# sheet1.net
KiCad netlist of a schematic drawn in EAGLE
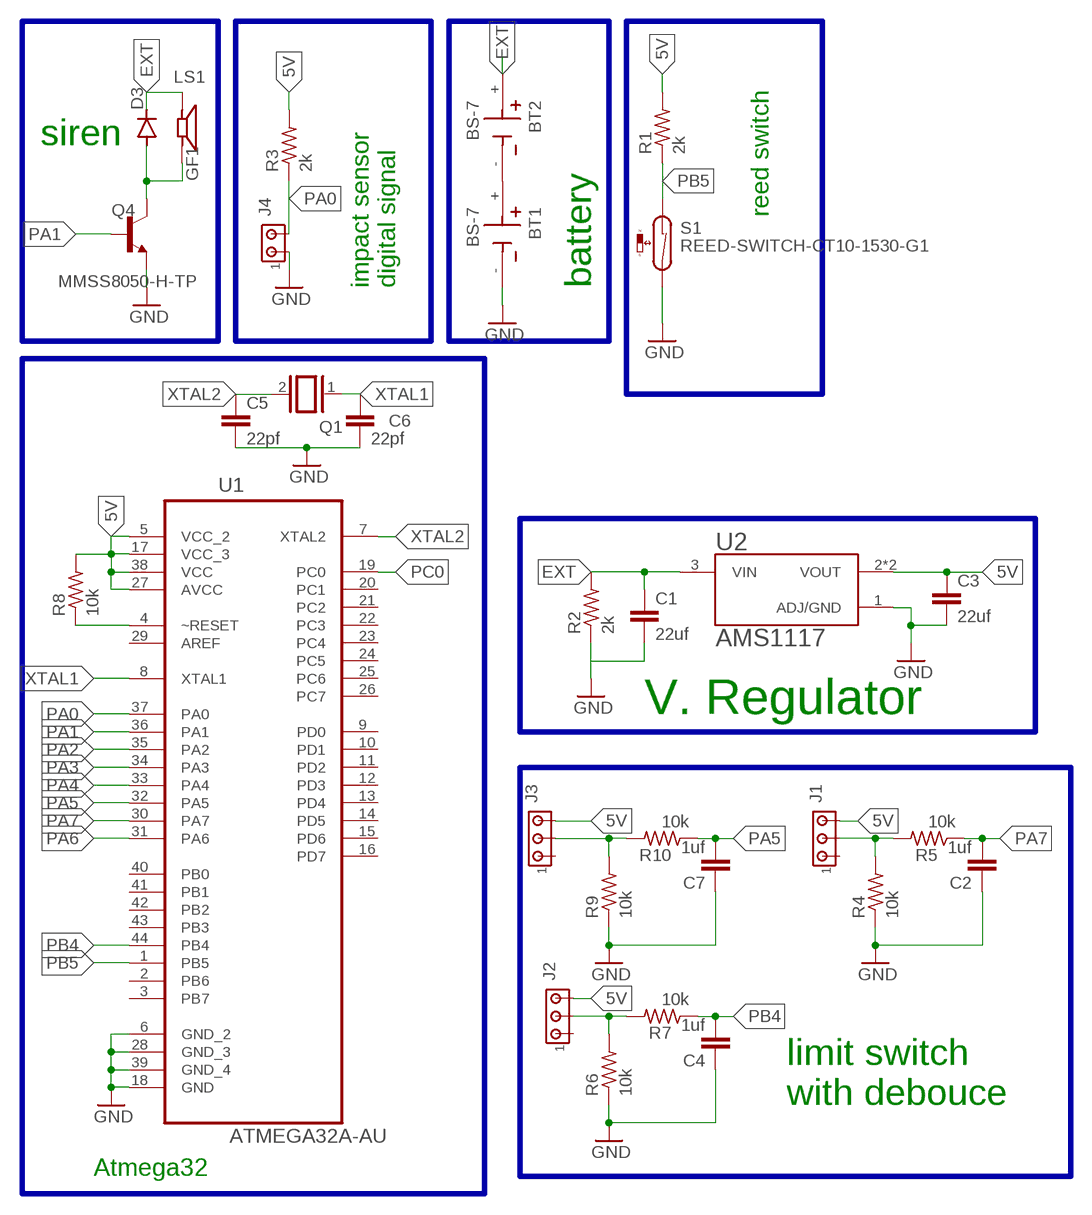
[diagram p0: schematic, sheet 1]

(export (version "E")
  (design (tool "Eeschema 10.0.6"))
  (components
    (comp (ref "BT1")
      (value "BS-7")
      (footprint "eagle-import:BAT_BS-7")
      (fields (field (name "MF") "MPD _Memory"))
      (libsource (lib "eagle-import") (part "BS-7"))
    )
    (comp (ref "BT2")
      (value "BS-7")
      (footprint "eagle-import:BAT_BS-7")
      (fields (field (name "MF") "MPD _Memory"))
      (libsource (lib "eagle-import") (part "BS-7"))
    )
    (comp (ref "C1")
      (value "22uf")
      (footprint "eagle-import:C1206")
      (libsource (lib "eagle-import") (part "C-EUC1206"))
    )
    (comp (ref "C2")
      (value "1uf")
      (footprint "eagle-import:C1206")
      (libsource (lib "eagle-import") (part "C-EUC1206"))
    )
    (comp (ref "C3")
      (value "22uf")
      (footprint "eagle-import:C1206")
      (libsource (lib "eagle-import") (part "C-EUC1206"))
    )
    (comp (ref "C4")
      (value "1uf")
      (footprint "eagle-import:C1206")
      (libsource (lib "eagle-import") (part "C-EUC1206"))
    )
    (comp (ref "C5")
      (value "22pf")
      (footprint "eagle-import:C1206")
      (libsource (lib "eagle-import") (part "C-EUC1206"))
    )
    (comp (ref "C6")
      (value "22pf")
      (footprint "eagle-import:C1206")
      (libsource (lib "eagle-import") (part "C-EUC1206"))
    )
    (comp (ref "C7")
      (value "1uf")
      (footprint "eagle-import:C1206")
      (libsource (lib "eagle-import") (part "C-EUC1206"))
    )
    (comp (ref "D3")
      (value "GF1")
      (footprint "eagle-import:SMA-DO214AC")
      (libsource (lib "eagle-import") (part "GF1"))
    )
    (comp (ref "J1")
      (value "MTA03-100")
      (footprint "eagle-import:10X03MTA")
      (libsource (lib "eagle-import") (part "MTA03-100"))
    )
    (comp (ref "J2")
      (value "MTA03-100")
      (footprint "eagle-import:10X03MTA")
      (libsource (lib "eagle-import") (part "MTA03-100"))
    )
    (comp (ref "J3")
      (value "MTA03-100")
      (footprint "eagle-import:10X03MTA")
      (libsource (lib "eagle-import") (part "MTA03-100"))
    )
    (comp (ref "J4")
      (value "MTA02-100")
      (footprint "eagle-import:10X02MTA")
      (libsource (lib "eagle-import") (part "MTA02-100"))
    )
    (comp (ref "LS1")
      (value "CEP-1152")
      (footprint "eagle-import:CUI_CEP-1152")
      (fields (field (name "MF") "CUI Devices"))
      (libsource (lib "eagle-import") (part "CEP-1152"))
    )
    (comp (ref "Q1")
      (value "XTAL/S")
      (footprint "eagle-import:QS")
      (libsource (lib "eagle-import") (part "XTAL/S"))
    )
    (comp (ref "Q4")
      (value "MMSS8050-H-TP")
      (footprint "eagle-import:TRANS_MMSS8050-H-TP")
      (fields (field (name "MF") "Micro Commercial"))
      (libsource (lib "eagle-import") (part "MMSS8050-H-TP"))
    )
    (comp (ref "R1")
      (value "2k")
      (footprint "eagle-import:R1206")
      (libsource (lib "eagle-import") (part "R-US_R1206"))
    )
    (comp (ref "R2")
      (value "2k")
      (footprint "eagle-import:R1206")
      (libsource (lib "eagle-import") (part "R-US_R1206"))
    )
    (comp (ref "R3")
      (value "2k")
      (footprint "eagle-import:R1206")
      (libsource (lib "eagle-import") (part "R-US_R1206"))
    )
    (comp (ref "R4")
      (value "10k")
      (footprint "eagle-import:R1206")
      (libsource (lib "eagle-import") (part "R-US_R1206"))
    )
    (comp (ref "R5")
      (value "10k")
      (footprint "eagle-import:R1206")
      (libsource (lib "eagle-import") (part "R-US_R1206"))
    )
    (comp (ref "R6")
      (value "10k")
      (footprint "eagle-import:R1206")
      (libsource (lib "eagle-import") (part "R-US_R1206"))
    )
    (comp (ref "R7")
      (value "10k")
      (footprint "eagle-import:R1206")
      (libsource (lib "eagle-import") (part "R-US_R1206"))
    )
    (comp (ref "R8")
      (value "10k")
      (footprint "eagle-import:R1206")
      (libsource (lib "eagle-import") (part "R-US_R1206"))
    )
    (comp (ref "R9")
      (value "10k")
      (footprint "eagle-import:R1206")
      (libsource (lib "eagle-import") (part "R-US_R1206"))
    )
    (comp (ref "R10")
      (value "10k")
      (footprint "eagle-import:R1206")
      (libsource (lib "eagle-import") (part "R-US_R1206"))
    )
    (comp (ref "S1")
      (value "REED-SWITCH-CT10-1530-G1")
      (footprint "eagle-import:CT10-G1")
      (fields (field (name "MF") "COTO TECHNOLOGY") (field (name "MPN") "CT10-1530-G1"))
      (libsource (lib "eagle-import") (part "REED-SWITCH-CT10-1530-G1"))
    )
    (comp (ref "U1")
      (value "ATMEGA32A-AU")
      (footprint "eagle-import:QFP80P1200X1200X120-44N")
      (fields (field (name "MF") "Microchip"))
      (libsource (lib "eagle-import") (part "ATMEGA32A-AU"))
    )
    (comp (ref "U2")
      (value "AMS1117")
      (footprint "eagle-import:SOT229P700X180-4N")
      (fields (field (name "MF") "Seeed Technology"))
      (libsource (lib "eagle-import") (part "AMS1117"))
    )
  )
  (nets
    (net (code "1") (name "5V") (class "Default")
      (node (ref "C3") (pin "1") (pinfunction "1_1") (pintype "passive"))
      (node (ref "J1") (pin "3") (pinfunction "3_3") (pintype "passive"))
      (node (ref "J2") (pin "3") (pinfunction "3_3") (pintype "passive"))
      (node (ref "J3") (pin "3") (pinfunction "3_3") (pintype "passive"))
      (node (ref "R1") (pin "2") (pinfunction "2_2") (pintype "passive"))
      (node (ref "R3") (pin "2") (pinfunction "2_2") (pintype "passive"))
      (node (ref "R8") (pin "2") (pinfunction "2_2") (pintype "passive"))
      (node (ref "U1") (pin "17") (pinfunction "VCC_3_17") (pintype "power_in"))
      (node (ref "U1") (pin "27") (pinfunction "AVCC_27") (pintype "power_in"))
      (node (ref "U1") (pin "38") (pinfunction "VCC_38") (pintype "power_in"))
      (node (ref "U1") (pin "5") (pinfunction "VCC_2_5") (pintype "power_in"))
      (node (ref "U2") (pin "2") (pinfunction "VOUT_2") (pintype "output"))
      (node (ref "U2") (pin "4") (pinfunction "VOUT_4") (pintype "output"))
    )
    (net (code "2") (name "EXT") (class "Default")
      (node (ref "BT2") (pin "+") (pinfunction "+_+") (pintype "passive"))
      (node (ref "C1") (pin "1") (pinfunction "1_1") (pintype "passive"))
      (node (ref "D3") (pin "K") (pinfunction "C_K") (pintype "passive"))
      (node (ref "LS1") (pin "1") (pinfunction "1_1") (pintype "passive"))
      (node (ref "R2") (pin "2") (pinfunction "2_2") (pintype "passive"))
      (node (ref "U2") (pin "3") (pinfunction "VIN_3") (pintype "input"))
    )
    (net (code "3") (name "GND") (class "Default")
      (node (ref "BT1") (pin "-") (pinfunction "-_-") (pintype "passive"))
      (node (ref "C1") (pin "2") (pinfunction "2_2") (pintype "passive"))
      (node (ref "C2") (pin "1") (pinfunction "1_1") (pintype "passive"))
      (node (ref "C3") (pin "2") (pinfunction "2_2") (pintype "passive"))
      (node (ref "C4") (pin "1") (pinfunction "1_1") (pintype "passive"))
      (node (ref "C5") (pin "2") (pinfunction "2_2") (pintype "passive"))
      (node (ref "C6") (pin "2") (pinfunction "2_2") (pintype "passive"))
      (node (ref "C7") (pin "1") (pinfunction "1_1") (pintype "passive"))
      (node (ref "J4") (pin "1") (pinfunction "1_1") (pintype "passive"))
      (node (ref "Q4") (pin "2") (pinfunction "E_2") (pintype "passive"))
      (node (ref "R2") (pin "1") (pinfunction "1_1") (pintype "passive"))
      (node (ref "R4") (pin "1") (pinfunction "1_1") (pintype "passive"))
      (node (ref "R6") (pin "1") (pinfunction "1_1") (pintype "passive"))
      (node (ref "R9") (pin "1") (pinfunction "1_1") (pintype "passive"))
      (node (ref "S1") (pin "2") (pinfunction "2_2") (pintype "passive"))
      (node (ref "U1") (pin "18") (pinfunction "GND_18") (pintype "passive"))
      (node (ref "U1") (pin "28") (pinfunction "GND_3_28") (pintype "passive"))
      (node (ref "U1") (pin "39") (pinfunction "GND_4_39") (pintype "passive"))
      (node (ref "U1") (pin "6") (pinfunction "GND_2_6") (pintype "passive"))
      (node (ref "U2") (pin "1") (pinfunction "ADJ/GND_1") (pintype "power_in"))
    )
    (net (code "4") (name "Net-(BT1-Pad+)") (class "Default")
      (node (ref "BT1") (pin "+") (pinfunction "+_+") (pintype "passive"))
      (node (ref "BT2") (pin "-") (pinfunction "-_-") (pintype "passive"))
    )
    (net (code "5") (name "Net-(J1-Pad2)") (class "Default")
      (node (ref "J1") (pin "2") (pinfunction "2_2") (pintype "passive"))
      (node (ref "R4") (pin "2") (pinfunction "2_2") (pintype "passive"))
      (node (ref "R5") (pin "2") (pinfunction "2_2") (pintype "passive"))
    )
    (net (code "6") (name "Net-(J2-Pad2)") (class "Default")
      (node (ref "J2") (pin "2") (pinfunction "2_2") (pintype "passive"))
      (node (ref "R6") (pin "2") (pinfunction "2_2") (pintype "passive"))
      (node (ref "R7") (pin "2") (pinfunction "2_2") (pintype "passive"))
    )
    (net (code "7") (name "Net-(J3-Pad2)") (class "Default")
      (node (ref "J3") (pin "2") (pinfunction "2_2") (pintype "passive"))
      (node (ref "R10") (pin "2") (pinfunction "2_2") (pintype "passive"))
      (node (ref "R9") (pin "2") (pinfunction "2_2") (pintype "passive"))
    )
    (net (code "8") (name "Net-(Q4-C)") (class "Default")
      (node (ref "D3") (pin "A") (pinfunction "A_A") (pintype "passive"))
      (node (ref "LS1") (pin "2") (pinfunction "2_2") (pintype "passive"))
      (node (ref "Q4") (pin "3") (pinfunction "C_3") (pintype "passive"))
    )
    (net (code "9") (name "Net-(U1-~{RESET})") (class "Default")
      (node (ref "R8") (pin "1") (pinfunction "1_1") (pintype "passive"))
      (node (ref "U1") (pin "4") (pinfunction "~{RESET}_4") (pintype "input"))
    )
    (net (code "10") (name "PA0") (class "Default")
      (node (ref "J4") (pin "2") (pinfunction "2_2") (pintype "passive"))
      (node (ref "R3") (pin "1") (pinfunction "1_1") (pintype "passive"))
      (node (ref "U1") (pin "37") (pinfunction "PA0_37") (pintype "bidirectional"))
    )
    (net (code "11") (name "PA1") (class "Default")
      (node (ref "Q4") (pin "1") (pinfunction "B_1") (pintype "passive"))
      (node (ref "U1") (pin "36") (pinfunction "PA1_36") (pintype "bidirectional"))
    )
    (net (code "12") (name "PA2") (class "Default")
      (node (ref "U1") (pin "35") (pinfunction "PA2_35") (pintype "bidirectional"))
    )
    (net (code "13") (name "PA3") (class "Default")
      (node (ref "U1") (pin "34") (pinfunction "PA3_34") (pintype "bidirectional"))
    )
    (net (code "14") (name "PA4") (class "Default")
      (node (ref "U1") (pin "33") (pinfunction "PA4_33") (pintype "bidirectional"))
    )
    (net (code "15") (name "PA5") (class "Default")
      (node (ref "C7") (pin "2") (pinfunction "2_2") (pintype "passive"))
      (node (ref "R10") (pin "1") (pinfunction "1_1") (pintype "passive"))
      (node (ref "U1") (pin "32") (pinfunction "PA5_32") (pintype "bidirectional"))
    )
    (net (code "16") (name "PA6") (class "Default")
      (node (ref "U1") (pin "31") (pinfunction "PA6_31") (pintype "bidirectional"))
    )
    (net (code "17") (name "PA7") (class "Default")
      (node (ref "C2") (pin "2") (pinfunction "2_2") (pintype "passive"))
      (node (ref "R5") (pin "1") (pinfunction "1_1") (pintype "passive"))
      (node (ref "U1") (pin "30") (pinfunction "PA7_30") (pintype "bidirectional"))
    )
    (net (code "18") (name "PB4") (class "Default")
      (node (ref "C4") (pin "2") (pinfunction "2_2") (pintype "passive"))
      (node (ref "R7") (pin "1") (pinfunction "1_1") (pintype "passive"))
      (node (ref "U1") (pin "44") (pinfunction "PB4_44") (pintype "bidirectional"))
    )
    (net (code "19") (name "PB5") (class "Default")
      (node (ref "R1") (pin "1") (pinfunction "1_1") (pintype "passive"))
      (node (ref "S1") (pin "1") (pinfunction "1_1") (pintype "passive"))
      (node (ref "U1") (pin "1") (pinfunction "PB5_1") (pintype "bidirectional"))
    )
    (net (code "20") (name "PC0") (class "Default")
      (node (ref "U1") (pin "19") (pinfunction "PC0_19") (pintype "bidirectional"))
    )
    (net (code "21") (name "XTAL1") (class "Default")
      (node (ref "C6") (pin "1") (pinfunction "1_1") (pintype "passive"))
      (node (ref "Q1") (pin "1") (pinfunction "1_1") (pintype "passive"))
      (node (ref "U1") (pin "8") (pinfunction "XTAL1_8") (pintype "input"))
    )
    (net (code "22") (name "XTAL2") (class "Default")
      (node (ref "C5") (pin "1") (pinfunction "1_1") (pintype "passive"))
      (node (ref "Q1") (pin "2") (pinfunction "2_2") (pintype "passive"))
      (node (ref "U1") (pin "7") (pinfunction "XTAL2_7") (pintype "output"))
    )
    (net (code "23") (name "unconnected-(J1-Pad1)") (class "Default")
      (node (ref "J1") (pin "1") (pinfunction "1_1") (pintype "passive"))
    )
    (net (code "24") (name "unconnected-(J2-Pad1)") (class "Default")
      (node (ref "J2") (pin "1") (pinfunction "1_1") (pintype "passive"))
    )
    (net (code "25") (name "unconnected-(J3-Pad1)") (class "Default")
      (node (ref "J3") (pin "1") (pinfunction "1_1") (pintype "passive"))
    )
    (net (code "26") (name "unconnected-(U1-AREF-Pad29)") (class "Default")
      (node (ref "U1") (pin "29") (pinfunction "AREF_29") (pintype "input"))
    )
    (net (code "27") (name "unconnected-(U1-PB0-Pad40)") (class "Default")
      (node (ref "U1") (pin "40") (pinfunction "PB0_40") (pintype "bidirectional"))
    )
    (net (code "28") (name "unconnected-(U1-PB1-Pad41)") (class "Default")
      (node (ref "U1") (pin "41") (pinfunction "PB1_41") (pintype "bidirectional"))
    )
    (net (code "29") (name "unconnected-(U1-PB2-Pad42)") (class "Default")
      (node (ref "U1") (pin "42") (pinfunction "PB2_42") (pintype "bidirectional"))
    )
    (net (code "30") (name "unconnected-(U1-PB3-Pad43)") (class "Default")
      (node (ref "U1") (pin "43") (pinfunction "PB3_43") (pintype "bidirectional"))
    )
    (net (code "31") (name "unconnected-(U1-PB6-Pad2)") (class "Default")
      (node (ref "U1") (pin "2") (pinfunction "PB6_2") (pintype "bidirectional"))
    )
    (net (code "32") (name "unconnected-(U1-PB7-Pad3)") (class "Default")
      (node (ref "U1") (pin "3") (pinfunction "PB7_3") (pintype "bidirectional"))
    )
    (net (code "33") (name "unconnected-(U1-PC1-Pad20)") (class "Default")
      (node (ref "U1") (pin "20") (pinfunction "PC1_20") (pintype "bidirectional"))
    )
    (net (code "34") (name "unconnected-(U1-PC2-Pad21)") (class "Default")
      (node (ref "U1") (pin "21") (pinfunction "PC2_21") (pintype "bidirectional"))
    )
    (net (code "35") (name "unconnected-(U1-PC3-Pad22)") (class "Default")
      (node (ref "U1") (pin "22") (pinfunction "PC3_22") (pintype "bidirectional"))
    )
    (net (code "36") (name "unconnected-(U1-PC4-Pad23)") (class "Default")
      (node (ref "U1") (pin "23") (pinfunction "PC4_23") (pintype "bidirectional"))
    )
    (net (code "37") (name "unconnected-(U1-PC5-Pad24)") (class "Default")
      (node (ref "U1") (pin "24") (pinfunction "PC5_24") (pintype "bidirectional"))
    )
    (net (code "38") (name "unconnected-(U1-PC6-Pad25)") (class "Default")
      (node (ref "U1") (pin "25") (pinfunction "PC6_25") (pintype "bidirectional"))
    )
    (net (code "39") (name "unconnected-(U1-PC7-Pad26)") (class "Default")
      (node (ref "U1") (pin "26") (pinfunction "PC7_26") (pintype "bidirectional"))
    )
    (net (code "40") (name "unconnected-(U1-PD0-Pad9)") (class "Default")
      (node (ref "U1") (pin "9") (pinfunction "PD0_9") (pintype "bidirectional"))
    )
    (net (code "41") (name "unconnected-(U1-PD1-Pad10)") (class "Default")
      (node (ref "U1") (pin "10") (pinfunction "PD1_10") (pintype "bidirectional"))
    )
    (net (code "42") (name "unconnected-(U1-PD2-Pad11)") (class "Default")
      (node (ref "U1") (pin "11") (pinfunction "PD2_11") (pintype "bidirectional"))
    )
    (net (code "43") (name "unconnected-(U1-PD3-Pad12)") (class "Default")
      (node (ref "U1") (pin "12") (pinfunction "PD3_12") (pintype "bidirectional"))
    )
    (net (code "44") (name "unconnected-(U1-PD4-Pad13)") (class "Default")
      (node (ref "U1") (pin "13") (pinfunction "PD4_13") (pintype "bidirectional"))
    )
    (net (code "45") (name "unconnected-(U1-PD5-Pad14)") (class "Default")
      (node (ref "U1") (pin "14") (pinfunction "PD5_14") (pintype "bidirectional"))
    )
    (net (code "46") (name "unconnected-(U1-PD6-Pad15)") (class "Default")
      (node (ref "U1") (pin "15") (pinfunction "PD6_15") (pintype "bidirectional"))
    )
    (net (code "47") (name "unconnected-(U1-PD7-Pad16)") (class "Default")
      (node (ref "U1") (pin "16") (pinfunction "PD7_16") (pintype "bidirectional"))
    )
  )
)
